# ECU_1v0.net
KiCad netlist of a schematic drawn in EAGLE
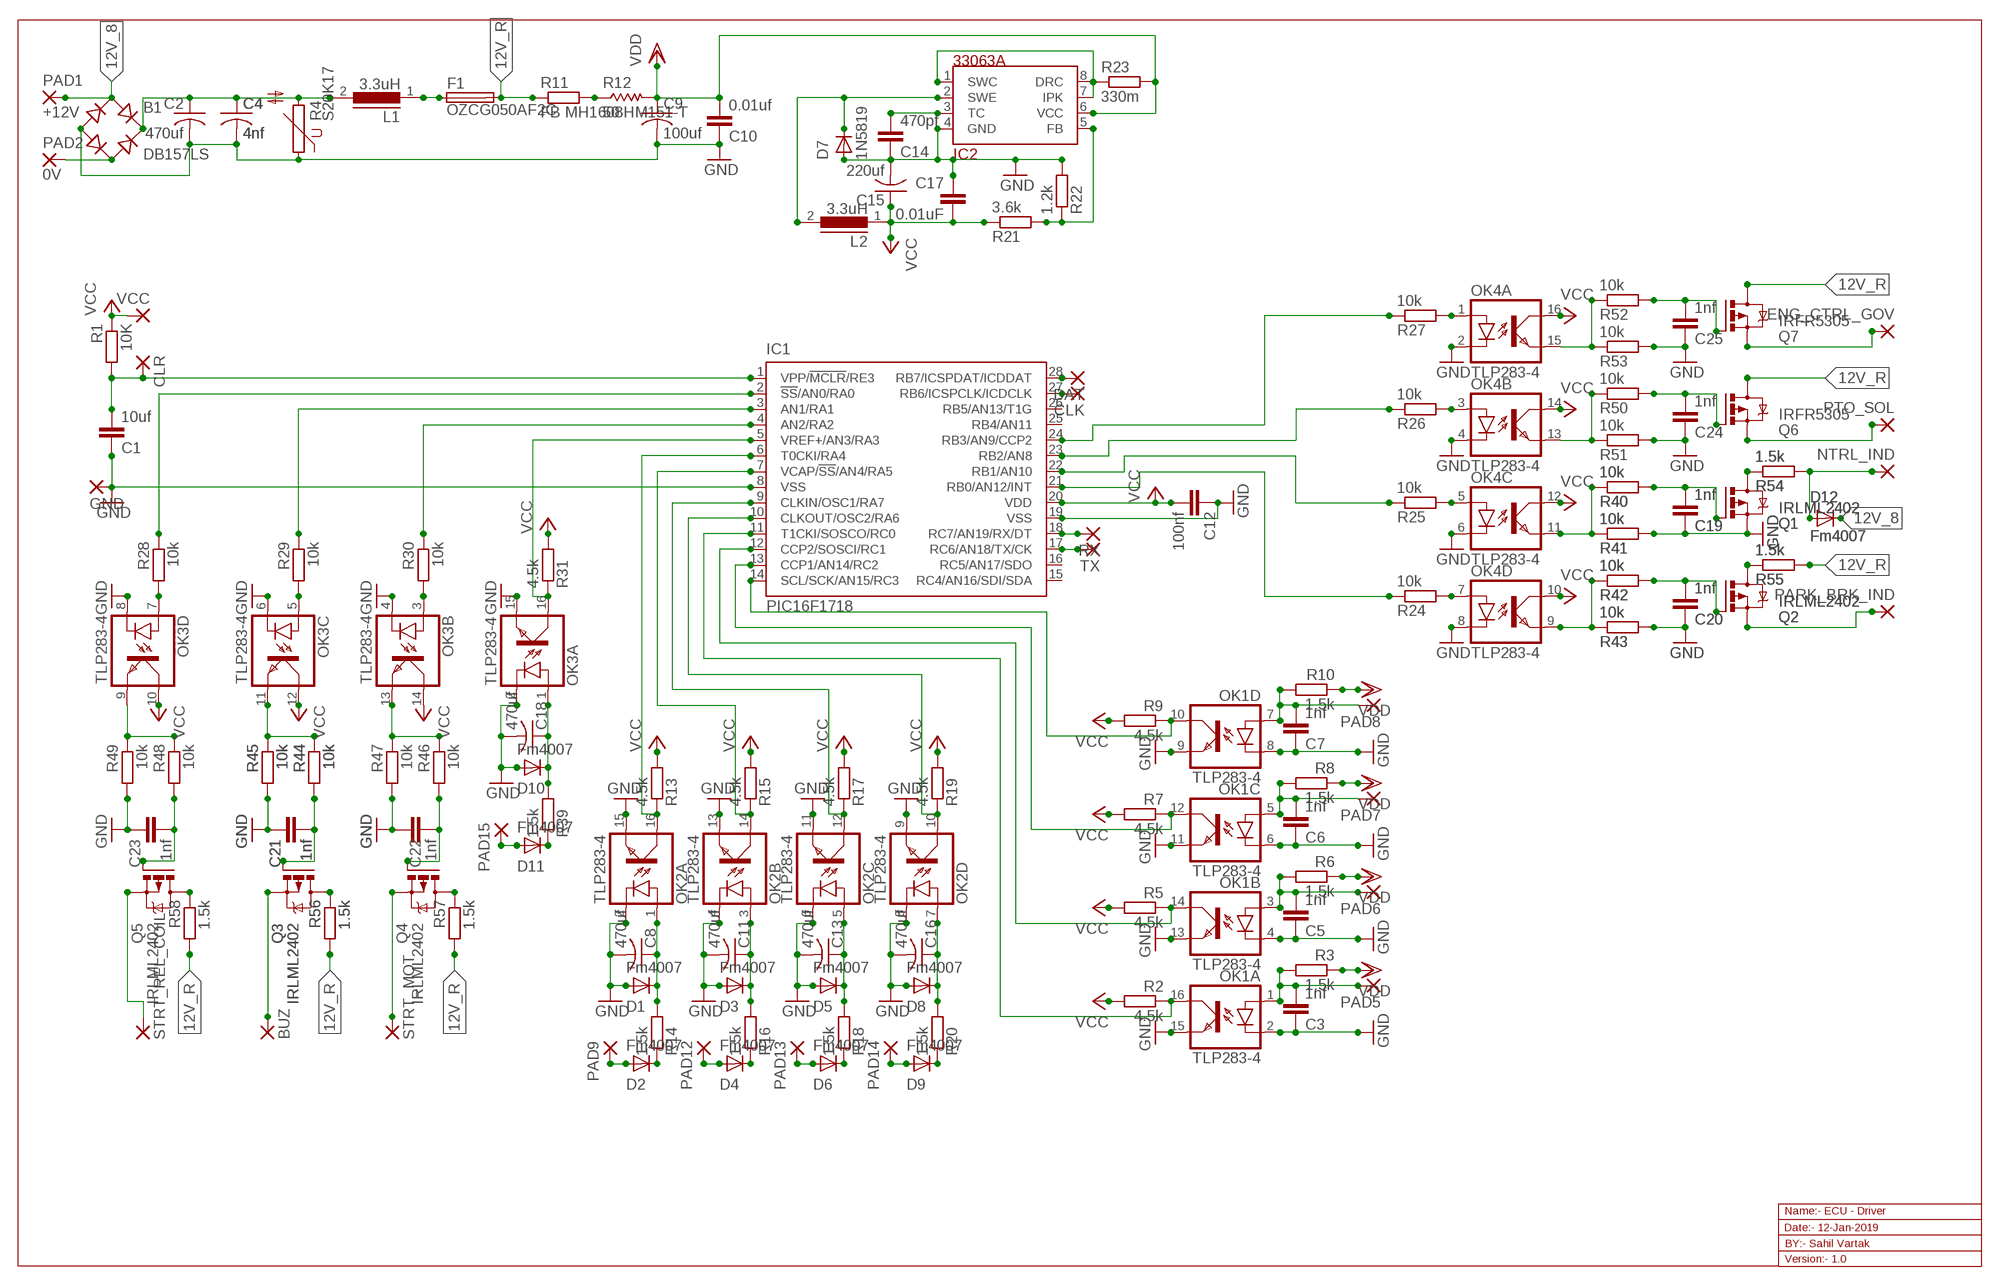
[diagram p0: schematic, sheet 1]

(export (version "E")
  (design (tool "Eeschema 10.0.6"))
  (components
    (comp (ref "B1")
      (value "DB157LS")
      (footprint "eagle-import:DBS")
      (libsource (lib "eagle-import") (part "DB?GS106"))
    )
    (comp (ref "BUZ")
      (value "2,54/1,1")
      (footprint "eagle-import:2,54_1,1")
      (libsource (lib "eagle-import") (part "2,54/1,1"))
    )
    (comp (ref "C1")
      (value "10uf")
      (footprint "eagle-import:C0603")
      (libsource (lib "eagle-import") (part "CC0603"))
    )
    (comp (ref "C2")
      (value "470uf")
      (footprint "eagle-import:C050-075X075")
      (libsource (lib "eagle-import") (part "resistor_C-US050-075X075"))
    )
    (comp (ref "C3")
      (value "1nf")
      (footprint "eagle-import:C0603")
      (libsource (lib "eagle-import") (part "CC0603"))
    )
    (comp (ref "C4")
      (value "4nf")
      (footprint "eagle-import:C050-045X075")
      (libsource (lib "eagle-import") (part "C-US050-045X075"))
    )
    (comp (ref "C5")
      (value "1nf")
      (footprint "eagle-import:C0603")
      (libsource (lib "eagle-import") (part "CC0603"))
    )
    (comp (ref "C6")
      (value "1nf")
      (footprint "eagle-import:C0603")
      (libsource (lib "eagle-import") (part "CC0603"))
    )
    (comp (ref "C7")
      (value "1nf")
      (footprint "eagle-import:C0603")
      (libsource (lib "eagle-import") (part "CC0603"))
    )
    (comp (ref "C8")
      (value "470uf")
      (footprint "eagle-import:C050-075X075")
      (libsource (lib "eagle-import") (part "resistor_C-US050-075X075"))
    )
    (comp (ref "C9")
      (value "100uf")
      (footprint "eagle-import:C025-025X050")
      (libsource (lib "eagle-import") (part "C-US025-025X050"))
    )
    (comp (ref "C10")
      (value "0.01uf")
      (footprint "eagle-import:C0603")
      (libsource (lib "eagle-import") (part "CC0603"))
    )
    (comp (ref "C11")
      (value "470uf")
      (footprint "eagle-import:C050-075X075")
      (libsource (lib "eagle-import") (part "resistor_C-US050-075X075"))
    )
    (comp (ref "C12")
      (value "100nf")
      (footprint "eagle-import:C0603")
      (libsource (lib "eagle-import") (part "CC0603"))
    )
    (comp (ref "C13")
      (value "470uf")
      (footprint "eagle-import:C050-075X075")
      (libsource (lib "eagle-import") (part "resistor_C-US050-075X075"))
    )
    (comp (ref "C14")
      (value "470pf")
      (footprint "eagle-import:C0603")
      (libsource (lib "eagle-import") (part "CC0603"))
    )
    (comp (ref "C15")
      (value "220uf")
      (footprint "eagle-import:C025-025X050")
      (libsource (lib "eagle-import") (part "C-US025-025X050"))
    )
    (comp (ref "C16")
      (value "470uf")
      (footprint "eagle-import:C050-075X075")
      (libsource (lib "eagle-import") (part "resistor_C-US050-075X075"))
    )
    (comp (ref "C17")
      (value "0.01uF")
      (footprint "eagle-import:C0603")
      (libsource (lib "eagle-import") (part "CC0603"))
    )
    (comp (ref "C18")
      (value "470uf")
      (footprint "eagle-import:C050-075X075")
      (libsource (lib "eagle-import") (part "resistor_C-US050-075X075"))
    )
    (comp (ref "C19")
      (value "1nf")
      (footprint "eagle-import:C0603")
      (libsource (lib "eagle-import") (part "CC0603"))
    )
    (comp (ref "C20")
      (value "1nf")
      (footprint "eagle-import:C0603")
      (libsource (lib "eagle-import") (part "CC0603"))
    )
    (comp (ref "C21")
      (value "1nf")
      (footprint "eagle-import:C0603")
      (libsource (lib "eagle-import") (part "CC0603"))
    )
    (comp (ref "C22")
      (value "1nf")
      (footprint "eagle-import:C0603")
      (libsource (lib "eagle-import") (part "CC0603"))
    )
    (comp (ref "C23")
      (value "1nf")
      (footprint "eagle-import:C0603")
      (libsource (lib "eagle-import") (part "CC0603"))
    )
    (comp (ref "C24")
      (value "1nf")
      (footprint "eagle-import:C0603")
      (libsource (lib "eagle-import") (part "CC0603"))
    )
    (comp (ref "C25")
      (value "1nf")
      (footprint "eagle-import:C0603")
      (libsource (lib "eagle-import") (part "CC0603"))
    )
    (comp (ref "CLK")
      (value "1,6/0,8")
      (footprint "eagle-import:1,6_0,8")
      (libsource (lib "eagle-import") (part "1,6/0,8"))
    )
    (comp (ref "CLR")
      (value "1,6/0,8")
      (footprint "eagle-import:1,6_0,8")
      (libsource (lib "eagle-import") (part "1,6/0,8"))
    )
    (comp (ref "D1")
      (value "Fm4007")
      (footprint "eagle-import:SMA-DO214AC")
      (libsource (lib "eagle-import") (part "GF1"))
    )
    (comp (ref "D2")
      (value "Fm4007")
      (footprint "eagle-import:SMA-DO214AC")
      (libsource (lib "eagle-import") (part "GF1"))
    )
    (comp (ref "D3")
      (value "Fm4007")
      (footprint "eagle-import:SMA-DO214AC")
      (libsource (lib "eagle-import") (part "GF1"))
    )
    (comp (ref "D4")
      (value "Fm4007")
      (footprint "eagle-import:SMA-DO214AC")
      (libsource (lib "eagle-import") (part "GF1"))
    )
    (comp (ref "D5")
      (value "Fm4007")
      (footprint "eagle-import:SMA-DO214AC")
      (libsource (lib "eagle-import") (part "GF1"))
    )
    (comp (ref "D6")
      (value "Fm4007")
      (footprint "eagle-import:SMA-DO214AC")
      (libsource (lib "eagle-import") (part "GF1"))
    )
    (comp (ref "D7")
      (value "1N5819")
      (footprint "eagle-import:SMA-DO214AC")
      (libsource (lib "eagle-import") (part "GF1"))
    )
    (comp (ref "D8")
      (value "Fm4007")
      (footprint "eagle-import:SMA-DO214AC")
      (libsource (lib "eagle-import") (part "GF1"))
    )
    (comp (ref "D9")
      (value "Fm4007")
      (footprint "eagle-import:SMA-DO214AC")
      (libsource (lib "eagle-import") (part "GF1"))
    )
    (comp (ref "D10")
      (value "Fm4007")
      (footprint "eagle-import:SMA-DO214AC")
      (libsource (lib "eagle-import") (part "GF1"))
    )
    (comp (ref "D11")
      (value "Fm4007")
      (footprint "eagle-import:SMA-DO214AC")
      (libsource (lib "eagle-import") (part "GF1"))
    )
    (comp (ref "D12")
      (value "Fm4007")
      (footprint "eagle-import:SMA-DO214AC")
      (libsource (lib "eagle-import") (part "GF1"))
    )
    (comp (ref "DAT")
      (value "1,6/0,8")
      (footprint "eagle-import:1,6_0,8")
      (libsource (lib "eagle-import") (part "1,6/0,8"))
    )
    (comp (ref "ENG_CTRL_GOV")
      (value "2,54/1,1")
      (footprint "eagle-import:2,54_1,1")
      (libsource (lib "eagle-import") (part "2,54/1,1"))
    )
    (comp (ref "F1")
      (value "OZCG050AF2C")
      (footprint "eagle-import:RES_FUSE")
      (libsource (lib "eagle-import") (part "RES_FUSE"))
    )
    (comp (ref "GND")
      (value "1,6/0,8")
      (footprint "eagle-import:1,6_0,8")
      (libsource (lib "eagle-import") (part "1,6/0,8"))
    )
    (comp (ref "IC1")
      (value "PIC16F1718")
      (footprint "eagle-import:SO28W")
      (libsource (lib "eagle-import") (part "PIC16F1516/18SO"))
    )
    (comp (ref "IC2")
      (value "33063A")
      (footprint "eagle-import:D_R-PDSO-G8")
      (libsource (lib "eagle-import") (part "33063A"))
    )
    (comp (ref "L1")
      (value "3.3uH")
      (footprint "eagle-import:82114R")
      (libsource (lib "eagle-import") (part "82114R"))
    )
    (comp (ref "L2")
      (value "3.3uH")
      (footprint "eagle-import:82114R")
      (libsource (lib "eagle-import") (part "82114R"))
    )
    (comp (ref "NTRL_IND")
      (value "2,54/1,1")
      (footprint "eagle-import:2,54_1,1")
      (libsource (lib "eagle-import") (part "2,54/1,1"))
    )
    (comp (ref "OK1")
      (value "TLP283-4")
      (footprint "eagle-import:MINI-FLAT-16")
      (libsource (lib "eagle-import") (part "TLP283-4"))
    )
    (comp (ref "OK2")
      (value "TLP283-4")
      (footprint "eagle-import:MINI-FLAT-16")
      (libsource (lib "eagle-import") (part "TLP283-4"))
    )
    (comp (ref "OK3")
      (value "TLP283-4")
      (footprint "eagle-import:MINI-FLAT-16")
      (libsource (lib "eagle-import") (part "TLP283-4"))
    )
    (comp (ref "OK4")
      (value "TLP283-4")
      (footprint "eagle-import:MINI-FLAT-16")
      (libsource (lib "eagle-import") (part "TLP283-4"))
    )
    (comp (ref "PAD1")
      (value "+12V")
      (footprint "eagle-import:2,54_1,1")
      (libsource (lib "eagle-import") (part "2,54/1,1"))
    )
    (comp (ref "PAD2")
      (value "0V")
      (footprint "eagle-import:2,54_1,1")
      (libsource (lib "eagle-import") (part "2,54/1,1"))
    )
    (comp (ref "PAD5")
      (value "2,54/1,1")
      (footprint "eagle-import:2,54_1,1")
      (libsource (lib "eagle-import") (part "2,54/1,1"))
    )
    (comp (ref "PAD6")
      (value "2,54/1,1")
      (footprint "eagle-import:2,54_1,1")
      (libsource (lib "eagle-import") (part "2,54/1,1"))
    )
    (comp (ref "PAD7")
      (value "2,54/1,1")
      (footprint "eagle-import:2,54_1,1")
      (libsource (lib "eagle-import") (part "2,54/1,1"))
    )
    (comp (ref "PAD8")
      (value "2,54/1,1")
      (footprint "eagle-import:2,54_1,1")
      (libsource (lib "eagle-import") (part "2,54/1,1"))
    )
    (comp (ref "PAD9")
      (value "2,54/1,1")
      (footprint "eagle-import:2,54_1,1")
      (libsource (lib "eagle-import") (part "2,54/1,1"))
    )
    (comp (ref "PAD12")
      (value "2,54/1,1")
      (footprint "eagle-import:2,54_1,1")
      (libsource (lib "eagle-import") (part "2,54/1,1"))
    )
    (comp (ref "PAD13")
      (value "2,54/1,1")
      (footprint "eagle-import:2,54_1,1")
      (libsource (lib "eagle-import") (part "2,54/1,1"))
    )
    (comp (ref "PAD14")
      (value "2,54/1,1")
      (footprint "eagle-import:2,54_1,1")
      (libsource (lib "eagle-import") (part "2,54/1,1"))
    )
    (comp (ref "PAD15")
      (value "2,54/1,1")
      (footprint "eagle-import:2,54_1,1")
      (libsource (lib "eagle-import") (part "2,54/1,1"))
    )
    (comp (ref "PARK_BRK_IND")
      (value "2,54/1,1")
      (footprint "eagle-import:2,54_1,1")
      (libsource (lib "eagle-import") (part "2,54/1,1"))
    )
    (comp (ref "PTO_SOL")
      (value "2,54/1,1")
      (footprint "eagle-import:2,54_1,1")
      (libsource (lib "eagle-import") (part "2,54/1,1"))
    )
    (comp (ref "Q1")
      (value "IRLML2402")
      (footprint "eagle-import:MICRO3")
      (libsource (lib "eagle-import") (part "IRLML5203"))
    )
    (comp (ref "Q2")
      (value "IRLML2402")
      (footprint "eagle-import:MICRO3")
      (libsource (lib "eagle-import") (part "IRLML5203"))
    )
    (comp (ref "Q3")
      (value "IRLML2402")
      (footprint "eagle-import:MICRO3")
      (libsource (lib "eagle-import") (part "IRLML5203"))
    )
    (comp (ref "Q4")
      (value "IRLML2402")
      (footprint "eagle-import:MICRO3")
      (libsource (lib "eagle-import") (part "IRLML5203"))
    )
    (comp (ref "Q5")
      (value "IRLML2402")
      (footprint "eagle-import:MICRO3")
      (libsource (lib "eagle-import") (part "IRLML5203"))
    )
    (comp (ref "Q6")
      (value "IRFR5305")
      (footprint "eagle-import:D-PAK_TO252AA")
      (libsource (lib "eagle-import") (part "IRF?5305R"))
    )
    (comp (ref "Q7")
      (value "IRFR5305")
      (footprint "eagle-import:D-PAK_TO252AA")
      (libsource (lib "eagle-import") (part "IRF?5305R"))
    )
    (comp (ref "R1")
      (value "10K")
      (footprint "eagle-import:R0603")
      (libsource (lib "eagle-import") (part "RR0603"))
    )
    (comp (ref "R2")
      (value "4.5k")
      (footprint "eagle-import:R0603")
      (libsource (lib "eagle-import") (part "RR0603"))
    )
    (comp (ref "R3")
      (value "1.5k")
      (footprint "eagle-import:R0603")
      (libsource (lib "eagle-import") (part "RR0603"))
    )
    (comp (ref "R4")
      (value "S20K17")
      (footprint "eagle-import:S14K17")
      (libsource (lib "eagle-import") (part "S14K17"))
    )
    (comp (ref "R5")
      (value "4.5k")
      (footprint "eagle-import:R0603")
      (libsource (lib "eagle-import") (part "RR0603"))
    )
    (comp (ref "R6")
      (value "1.5k")
      (footprint "eagle-import:R0603")
      (libsource (lib "eagle-import") (part "RR0603"))
    )
    (comp (ref "R7")
      (value "4.5k")
      (footprint "eagle-import:R0603")
      (libsource (lib "eagle-import") (part "RR0603"))
    )
    (comp (ref "R8")
      (value "1.5k")
      (footprint "eagle-import:R0603")
      (libsource (lib "eagle-import") (part "RR0603"))
    )
    (comp (ref "R9")
      (value "4.5k")
      (footprint "eagle-import:R0603")
      (libsource (lib "eagle-import") (part "RR0603"))
    )
    (comp (ref "R10")
      (value "1.5k")
      (footprint "eagle-import:R0603")
      (libsource (lib "eagle-import") (part "RR0603"))
    )
    (comp (ref "R11")
      (value "FB MH1608HM151-T")
      (footprint "eagle-import:R0603")
      (libsource (lib "eagle-import") (part "R-EU_R0603"))
    )
    (comp (ref "R12")
      (value "50")
      (footprint "eagle-import:WSC2515")
      (libsource (lib "eagle-import") (part "R-US_WSC2515"))
    )
    (comp (ref "R13")
      (value "4.5k")
      (footprint "eagle-import:R0603")
      (libsource (lib "eagle-import") (part "RR0603"))
    )
    (comp (ref "R14")
      (value "1.5k")
      (footprint "eagle-import:R0603")
      (libsource (lib "eagle-import") (part "RR0603"))
    )
    (comp (ref "R15")
      (value "4.5k")
      (footprint "eagle-import:R0603")
      (libsource (lib "eagle-import") (part "RR0603"))
    )
    (comp (ref "R16")
      (value "1.5k")
      (footprint "eagle-import:R0603")
      (libsource (lib "eagle-import") (part "RR0603"))
    )
    (comp (ref "R17")
      (value "4.5k")
      (footprint "eagle-import:R0603")
      (libsource (lib "eagle-import") (part "RR0603"))
    )
    (comp (ref "R18")
      (value "1.5k")
      (footprint "eagle-import:R0603")
      (libsource (lib "eagle-import") (part "RR0603"))
    )
    (comp (ref "R19")
      (value "4.5k")
      (footprint "eagle-import:R0603")
      (libsource (lib "eagle-import") (part "RR0603"))
    )
    (comp (ref "R20")
      (value "1.5k")
      (footprint "eagle-import:R0603")
      (libsource (lib "eagle-import") (part "RR0603"))
    )
    (comp (ref "R21")
      (value "3.6k")
      (footprint "eagle-import:R0603")
      (libsource (lib "eagle-import") (part "RR0603"))
    )
    (comp (ref "R22")
      (value "1.2k")
      (footprint "eagle-import:R0603")
      (libsource (lib "eagle-import") (part "RR0603"))
    )
    (comp (ref "R23")
      (value "330m")
      (footprint "eagle-import:R2010")
      (libsource (lib "eagle-import") (part "RR2010"))
    )
    (comp (ref "R24")
      (value "10k")
      (footprint "eagle-import:R0603")
      (libsource (lib "eagle-import") (part "RR0603"))
    )
    (comp (ref "R25")
      (value "10k")
      (footprint "eagle-import:R0603")
      (libsource (lib "eagle-import") (part "RR0603"))
    )
    (comp (ref "R26")
      (value "10k")
      (footprint "eagle-import:R0603")
      (libsource (lib "eagle-import") (part "RR0603"))
    )
    (comp (ref "R27")
      (value "10k")
      (footprint "eagle-import:R0603")
      (libsource (lib "eagle-import") (part "RR0603"))
    )
    (comp (ref "R28")
      (value "10k")
      (footprint "eagle-import:R0603")
      (libsource (lib "eagle-import") (part "RR0603"))
    )
    (comp (ref "R29")
      (value "10k")
      (footprint "eagle-import:R0603")
      (libsource (lib "eagle-import") (part "RR0603"))
    )
    (comp (ref "R30")
      (value "10k")
      (footprint "eagle-import:R0603")
      (libsource (lib "eagle-import") (part "RR0603"))
    )
    (comp (ref "R31")
      (value "4.5k")
      (footprint "eagle-import:R0603")
      (libsource (lib "eagle-import") (part "RR0603"))
    )
    (comp (ref "R39")
      (value "1.5k")
      (footprint "eagle-import:R0603")
      (libsource (lib "eagle-import") (part "RR0603"))
    )
    (comp (ref "R40")
      (value "10k")
      (footprint "eagle-import:R0603")
      (libsource (lib "eagle-import") (part "RR0603"))
    )
    (comp (ref "R41")
      (value "10k")
      (footprint "eagle-import:R0603")
      (libsource (lib "eagle-import") (part "RR0603"))
    )
    (comp (ref "R42")
      (value "10k")
      (footprint "eagle-import:R0603")
      (libsource (lib "eagle-import") (part "RR0603"))
    )
    (comp (ref "R43")
      (value "10k")
      (footprint "eagle-import:R0603")
      (libsource (lib "eagle-import") (part "RR0603"))
    )
    (comp (ref "R44")
      (value "10k")
      (footprint "eagle-import:R0603")
      (libsource (lib "eagle-import") (part "RR0603"))
    )
    (comp (ref "R45")
      (value "10k")
      (footprint "eagle-import:R0603")
      (libsource (lib "eagle-import") (part "RR0603"))
    )
    (comp (ref "R46")
      (value "10k")
      (footprint "eagle-import:R0603")
      (libsource (lib "eagle-import") (part "RR0603"))
    )
    (comp (ref "R47")
      (value "10k")
      (footprint "eagle-import:R0603")
      (libsource (lib "eagle-import") (part "RR0603"))
    )
    (comp (ref "R48")
      (value "10k")
      (footprint "eagle-import:R0603")
      (libsource (lib "eagle-import") (part "RR0603"))
    )
    (comp (ref "R49")
      (value "10k")
      (footprint "eagle-import:R0603")
      (libsource (lib "eagle-import") (part "RR0603"))
    )
    (comp (ref "R50")
      (value "10k")
      (footprint "eagle-import:R0603")
      (libsource (lib "eagle-import") (part "RR0603"))
    )
    (comp (ref "R51")
      (value "10k")
      (footprint "eagle-import:R0603")
      (libsource (lib "eagle-import") (part "RR0603"))
    )
    (comp (ref "R52")
      (value "10k")
      (footprint "eagle-import:R0603")
      (libsource (lib "eagle-import") (part "RR0603"))
    )
    (comp (ref "R53")
      (value "10k")
      (footprint "eagle-import:R0603")
      (libsource (lib "eagle-import") (part "RR0603"))
    )
    (comp (ref "R54")
      (value "1.5k")
      (footprint "eagle-import:R0603")
      (libsource (lib "eagle-import") (part "RR0603"))
    )
    (comp (ref "R55")
      (value "1.5k")
      (footprint "eagle-import:R0603")
      (libsource (lib "eagle-import") (part "RR0603"))
    )
    (comp (ref "R56")
      (value "1.5k")
      (footprint "eagle-import:R0603")
      (libsource (lib "eagle-import") (part "RR0603"))
    )
    (comp (ref "R57")
      (value "1.5k")
      (footprint "eagle-import:R0603")
      (libsource (lib "eagle-import") (part "RR0603"))
    )
    (comp (ref "R58")
      (value "1.5k")
      (footprint "eagle-import:R0603")
      (libsource (lib "eagle-import") (part "RR0603"))
    )
    (comp (ref "RX")
      (value "1,6/0,8")
      (footprint "eagle-import:1,6_0,8")
      (libsource (lib "eagle-import") (part "1,6/0,8"))
    )
    (comp (ref "STRT_MOT")
      (value "2,54/1,1")
      (footprint "eagle-import:2,54_1,1")
      (libsource (lib "eagle-import") (part "2,54/1,1"))
    )
    (comp (ref "STRT_REL_COIL")
      (value "2,54/1,1")
      (footprint "eagle-import:2,54_1,1")
      (libsource (lib "eagle-import") (part "2,54/1,1"))
    )
    (comp (ref "TX")
      (value "1,6/0,8")
      (footprint "eagle-import:1,6_0,8")
      (libsource (lib "eagle-import") (part "1,6/0,8"))
    )
    (comp (ref "VCC")
      (value "1,6/0,8")
      (footprint "eagle-import:1,6_0,8")
      (libsource (lib "eagle-import") (part "1,6/0,8"))
    )
  )
  (nets
    (net (code "1") (name "12V_8") (class "Default")
      (node (ref "B1") (pin "AC1") (pinfunction "AC1_AC1") (pintype "passive"))
      (node (ref "D12") (pin "K") (pinfunction "C_K") (pintype "passive"))
      (node (ref "PAD1") (pin "1") (pinfunction "P_1") (pintype "passive"))
    )
    (net (code "2") (name "12V_R") (class "Default")
      (node (ref "F1") (pin "2") (pinfunction "4_2") (pintype "passive"))
      (node (ref "Q6") (pin "4") (pinfunction "D_4") (pintype "passive"))
      (node (ref "Q7") (pin "4") (pinfunction "D_4") (pintype "passive"))
      (node (ref "R11") (pin "1") (pinfunction "1_1") (pintype "passive"))
      (node (ref "R55") (pin "2") (pinfunction "2_2") (pintype "passive"))
      (node (ref "R56") (pin "2") (pinfunction "2_2") (pintype "passive"))
      (node (ref "R57") (pin "2") (pinfunction "2_2") (pintype "passive"))
      (node (ref "R58") (pin "2") (pinfunction "2_2") (pintype "passive"))
    )
    (net (code "3") (name "GND") (class "Default")
      (node (ref "B1") (pin "-") (pinfunction "-_-") (pintype "passive"))
      (node (ref "C1") (pin "1") (pinfunction "1_1") (pintype "passive"))
      (node (ref "C10") (pin "1") (pinfunction "1_1") (pintype "passive"))
      (node (ref "C11") (pin "2") (pinfunction "2_2") (pintype "passive"))
      (node (ref "C12") (pin "1") (pinfunction "1_1") (pintype "passive"))
      (node (ref "C13") (pin "2") (pinfunction "2_2") (pintype "passive"))
      (node (ref "C14") (pin "1") (pinfunction "1_1") (pintype "passive"))
      (node (ref "C15") (pin "2") (pinfunction "2_2") (pintype "passive"))
      (node (ref "C16") (pin "2") (pinfunction "2_2") (pintype "passive"))
      (node (ref "C17") (pin "1") (pinfunction "1_1") (pintype "passive"))
      (node (ref "C18") (pin "2") (pinfunction "2_2") (pintype "passive"))
      (node (ref "C19") (pin "1") (pinfunction "1_1") (pintype "passive"))
      (node (ref "C2") (pin "2") (pinfunction "2_2") (pintype "passive"))
      (node (ref "C20") (pin "1") (pinfunction "1_1") (pintype "passive"))
      (node (ref "C21") (pin "1") (pinfunction "1_1") (pintype "passive"))
      (node (ref "C22") (pin "1") (pinfunction "1_1") (pintype "passive"))
      (node (ref "C23") (pin "1") (pinfunction "1_1") (pintype "passive"))
      (node (ref "C24") (pin "1") (pinfunction "1_1") (pintype "passive"))
      (node (ref "C25") (pin "1") (pinfunction "1_1") (pintype "passive"))
      (node (ref "C3") (pin "1") (pinfunction "1_1") (pintype "passive"))
      (node (ref "C4") (pin "2") (pinfunction "2_2") (pintype "passive"))
      (node (ref "C5") (pin "1") (pinfunction "1_1") (pintype "passive"))
      (node (ref "C6") (pin "1") (pinfunction "1_1") (pintype "passive"))
      (node (ref "C7") (pin "1") (pinfunction "1_1") (pintype "passive"))
      (node (ref "C8") (pin "2") (pinfunction "2_2") (pintype "passive"))
      (node (ref "C9") (pin "2") (pinfunction "2_2") (pintype "passive"))
      (node (ref "D1") (pin "A") (pinfunction "A_A") (pintype "passive"))
      (node (ref "D10") (pin "A") (pinfunction "A_A") (pintype "passive"))
      (node (ref "D3") (pin "A") (pinfunction "A_A") (pintype "passive"))
      (node (ref "D5") (pin "A") (pinfunction "A_A") (pintype "passive"))
      (node (ref "D7") (pin "A") (pinfunction "A_A") (pintype "passive"))
      (node (ref "D8") (pin "A") (pinfunction "A_A") (pintype "passive"))
      (node (ref "GND") (pin "1") (pinfunction "P_1") (pintype "passive"))
      (node (ref "IC1") (pin "19") (pinfunction "VSS_19") (pintype "power_in"))
      (node (ref "IC1") (pin "8") (pinfunction "VSS_8") (pintype "power_in"))
      (node (ref "IC2") (pin "4") (pinfunction "GND_4") (pintype "bidirectional"))
      (node (ref "OK1") (pin "11") (pinfunction "EMIT_11") (pintype "passive"))
      (node (ref "OK1") (pin "13") (pinfunction "EMIT_13") (pintype "passive"))
      (node (ref "OK1") (pin "15") (pinfunction "EMIT_15") (pintype "passive"))
      (node (ref "OK1") (pin "2") (pinfunction "C_2") (pintype "passive"))
      (node (ref "OK1") (pin "4") (pinfunction "C_4") (pintype "passive"))
      (node (ref "OK1") (pin "6") (pinfunction "C_6") (pintype "passive"))
      (node (ref "OK1") (pin "8") (pinfunction "C_8") (pintype "passive"))
      (node (ref "OK1") (pin "9") (pinfunction "EMIT_9") (pintype "passive"))
      (node (ref "OK2") (pin "11") (pinfunction "EMIT_11") (pintype "passive"))
      (node (ref "OK2") (pin "13") (pinfunction "EMIT_13") (pintype "passive"))
      (node (ref "OK2") (pin "15") (pinfunction "EMIT_15") (pintype "passive"))
      (node (ref "OK2") (pin "2") (pinfunction "C_2") (pintype "passive"))
      (node (ref "OK2") (pin "4") (pinfunction "C_4") (pintype "passive"))
      (node (ref "OK2") (pin "6") (pinfunction "C_6") (pintype "passive"))
      (node (ref "OK2") (pin "8") (pinfunction "C_8") (pintype "passive"))
      (node (ref "OK2") (pin "9") (pinfunction "EMIT_9") (pintype "passive"))
      (node (ref "OK3") (pin "15") (pinfunction "EMIT_15") (pintype "passive"))
      (node (ref "OK3") (pin "2") (pinfunction "C_2") (pintype "passive"))
      (node (ref "OK3") (pin "4") (pinfunction "C_4") (pintype "passive"))
      (node (ref "OK3") (pin "6") (pinfunction "C_6") (pintype "passive"))
      (node (ref "OK3") (pin "8") (pinfunction "C_8") (pintype "passive"))
      (node (ref "OK4") (pin "2") (pinfunction "C_2") (pintype "passive"))
      (node (ref "OK4") (pin "4") (pinfunction "C_4") (pintype "passive"))
      (node (ref "OK4") (pin "6") (pinfunction "C_6") (pintype "passive"))
      (node (ref "OK4") (pin "8") (pinfunction "C_8") (pintype "passive"))
      (node (ref "Q1") (pin "2") (pinfunction "S_2") (pintype "passive"))
      (node (ref "R22") (pin "2") (pinfunction "2_2") (pintype "passive"))
      (node (ref "R4") (pin "1") (pinfunction "1_1") (pintype "passive"))
      (node (ref "R41") (pin "2") (pinfunction "2_2") (pintype "passive"))
      (node (ref "R43") (pin "2") (pinfunction "2_2") (pintype "passive"))
      (node (ref "R45") (pin "2") (pinfunction "2_2") (pintype "passive"))
      (node (ref "R47") (pin "2") (pinfunction "2_2") (pintype "passive"))
      (node (ref "R49") (pin "2") (pinfunction "2_2") (pintype "passive"))
      (node (ref "R51") (pin "2") (pinfunction "2_2") (pintype "passive"))
      (node (ref "R53") (pin "2") (pinfunction "2_2") (pintype "passive"))
    )
    (net (code "4") (name "Net-(B1-Pad+)") (class "Default")
      (node (ref "B1") (pin "+") (pinfunction "+_+") (pintype "passive"))
      (node (ref "C2") (pin "1") (pinfunction "1_1") (pintype "passive"))
      (node (ref "C4") (pin "1") (pinfunction "1_1") (pintype "passive"))
      (node (ref "L1") (pin "2") (pinfunction "2_2") (pintype "passive"))
      (node (ref "R4") (pin "2") (pinfunction "2_2") (pintype "passive"))
    )
    (net (code "5") (name "Net-(BUZ-P)") (class "Default")
      (node (ref "BUZ") (pin "1") (pinfunction "P_1") (pintype "passive"))
      (node (ref "Q3") (pin "2") (pinfunction "S_2") (pintype "passive"))
    )
    (net (code "6") (name "Net-(CLK-P)") (class "Default")
      (node (ref "CLK") (pin "1") (pinfunction "P_1") (pintype "passive"))
      (node (ref "IC1") (pin "27") (pinfunction "RB6/ICSPCLK/ICDCLK_27") (pintype "bidirectional"))
    )
    (net (code "7") (name "Net-(CLR-P)") (class "Default")
      (node (ref "C1") (pin "2") (pinfunction "2_2") (pintype "passive"))
      (node (ref "CLR") (pin "1") (pinfunction "P_1") (pintype "passive"))
      (node (ref "IC1") (pin "1") (pinfunction "VPP/~{MCLR}/RE3_1") (pintype "bidirectional"))
      (node (ref "R1") (pin "2") (pinfunction "2_2") (pintype "passive"))
    )
    (net (code "8") (name "Net-(D1-C)") (class "Default")
      (node (ref "C8") (pin "1") (pinfunction "1_1") (pintype "passive"))
      (node (ref "D1") (pin "K") (pinfunction "C_K") (pintype "passive"))
      (node (ref "OK2") (pin "1") (pinfunction "A_1") (pintype "passive"))
      (node (ref "R14") (pin "2") (pinfunction "2_2") (pintype "passive"))
    )
    (net (code "9") (name "Net-(D2-C)") (class "Default")
      (node (ref "D2") (pin "K") (pinfunction "C_K") (pintype "passive"))
      (node (ref "R14") (pin "1") (pinfunction "1_1") (pintype "passive"))
    )
    (net (code "10") (name "Net-(D3-C)") (class "Default")
      (node (ref "C11") (pin "1") (pinfunction "1_1") (pintype "passive"))
      (node (ref "D3") (pin "K") (pinfunction "C_K") (pintype "passive"))
      (node (ref "OK2") (pin "3") (pinfunction "A_3") (pintype "passive"))
      (node (ref "R16") (pin "2") (pinfunction "2_2") (pintype "passive"))
    )
    (net (code "11") (name "Net-(D4-C)") (class "Default")
      (node (ref "D4") (pin "K") (pinfunction "C_K") (pintype "passive"))
      (node (ref "R16") (pin "1") (pinfunction "1_1") (pintype "passive"))
    )
    (net (code "12") (name "Net-(D5-C)") (class "Default")
      (node (ref "C13") (pin "1") (pinfunction "1_1") (pintype "passive"))
      (node (ref "D5") (pin "K") (pinfunction "C_K") (pintype "passive"))
      (node (ref "OK2") (pin "5") (pinfunction "A_5") (pintype "passive"))
      (node (ref "R18") (pin "2") (pinfunction "2_2") (pintype "passive"))
    )
    (net (code "13") (name "Net-(D6-C)") (class "Default")
      (node (ref "D6") (pin "K") (pinfunction "C_K") (pintype "passive"))
      (node (ref "R18") (pin "1") (pinfunction "1_1") (pintype "passive"))
    )
    (net (code "14") (name "Net-(D7-C)") (class "Default")
      (node (ref "D7") (pin "K") (pinfunction "C_K") (pintype "passive"))
      (node (ref "IC2") (pin "2") (pinfunction "SWE_2") (pintype "bidirectional"))
      (node (ref "L2") (pin "2") (pinfunction "2_2") (pintype "passive"))
    )
    (net (code "15") (name "Net-(D8-C)") (class "Default")
      (node (ref "C16") (pin "1") (pinfunction "1_1") (pintype "passive"))
      (node (ref "D8") (pin "K") (pinfunction "C_K") (pintype "passive"))
      (node (ref "OK2") (pin "7") (pinfunction "A_7") (pintype "passive"))
      (node (ref "R20") (pin "2") (pinfunction "2_2") (pintype "passive"))
    )
    (net (code "16") (name "Net-(D9-C)") (class "Default")
      (node (ref "D9") (pin "K") (pinfunction "C_K") (pintype "passive"))
      (node (ref "R20") (pin "1") (pinfunction "1_1") (pintype "passive"))
    )
    (net (code "17") (name "Net-(D10-C)") (class "Default")
      (node (ref "C18") (pin "1") (pinfunction "1_1") (pintype "passive"))
      (node (ref "D10") (pin "K") (pinfunction "C_K") (pintype "passive"))
      (node (ref "OK3") (pin "1") (pinfunction "A_1") (pintype "passive"))
      (node (ref "R39") (pin "2") (pinfunction "2_2") (pintype "passive"))
    )
    (net (code "18") (name "Net-(D11-C)") (class "Default")
      (node (ref "D11") (pin "K") (pinfunction "C_K") (pintype "passive"))
      (node (ref "R39") (pin "1") (pinfunction "1_1") (pintype "passive"))
    )
    (net (code "19") (name "Net-(DAT-P)") (class "Default")
      (node (ref "DAT") (pin "1") (pinfunction "P_1") (pintype "passive"))
      (node (ref "IC1") (pin "28") (pinfunction "RB7/ICSPDAT/ICDDAT_28") (pintype "bidirectional"))
    )
    (net (code "20") (name "Net-(ENG_CTRL_GOV-P)") (class "Default")
      (node (ref "ENG_CTRL_GOV") (pin "1") (pinfunction "P_1") (pintype "passive"))
      (node (ref "Q7") (pin "3") (pinfunction "S_3") (pintype "passive"))
    )
    (net (code "21") (name "Net-(F1-3)") (class "Default")
      (node (ref "F1") (pin "1") (pinfunction "3_1") (pintype "passive"))
      (node (ref "L1") (pin "1") (pinfunction "1_1") (pintype "passive"))
    )
    (net (code "22") (name "Net-(IC1-AN1{slash}RA1)") (class "Default")
      (node (ref "IC1") (pin "3") (pinfunction "AN1/RA1_3") (pintype "bidirectional"))
      (node (ref "R29") (pin "1") (pinfunction "1_1") (pintype "passive"))
    )
    (net (code "23") (name "Net-(IC1-AN2{slash}RA2)") (class "Default")
      (node (ref "IC1") (pin "4") (pinfunction "AN2/RA2_4") (pintype "bidirectional"))
      (node (ref "R30") (pin "1") (pinfunction "1_1") (pintype "passive"))
    )
    (net (code "24") (name "Net-(IC1-CCP1{slash}AN14{slash}RC2)") (class "Default")
      (node (ref "IC1") (pin "13") (pinfunction "CCP1/AN14/RC2_13") (pintype "bidirectional"))
      (node (ref "OK1") (pin "12") (pinfunction "COL_12") (pintype "passive"))
      (node (ref "R7") (pin "1") (pinfunction "1_1") (pintype "passive"))
    )
    (net (code "25") (name "Net-(IC1-CCP2{slash}SOSCI{slash}RC1)") (class "Default")
      (node (ref "IC1") (pin "12") (pinfunction "CCP2/SOSCI/RC1_12") (pintype "bidirectional"))
      (node (ref "OK1") (pin "14") (pinfunction "COL_14") (pintype "passive"))
      (node (ref "R5") (pin "1") (pinfunction "1_1") (pintype "passive"))
    )
    (net (code "26") (name "Net-(IC1-CLKIN{slash}OSC1{slash}RA7)") (class "Default")
      (node (ref "IC1") (pin "9") (pinfunction "CLKIN/OSC1/RA7_9") (pintype "bidirectional"))
      (node (ref "OK2") (pin "12") (pinfunction "COL_12") (pintype "passive"))
      (node (ref "R17") (pin "1") (pinfunction "1_1") (pintype "passive"))
    )
    (net (code "27") (name "Net-(IC1-CLKOUT{slash}OSC2{slash}RA6)") (class "Default")
      (node (ref "IC1") (pin "10") (pinfunction "CLKOUT/OSC2/RA6_10") (pintype "bidirectional"))
      (node (ref "OK2") (pin "10") (pinfunction "COL_10") (pintype "passive"))
      (node (ref "R19") (pin "1") (pinfunction "1_1") (pintype "passive"))
    )
    (net (code "28") (name "Net-(IC1-RB0{slash}AN12{slash}INT)") (class "Default")
      (node (ref "IC1") (pin "21") (pinfunction "RB0/AN12/INT_21") (pintype "bidirectional"))
      (node (ref "R24") (pin "1") (pinfunction "1_1") (pintype "passive"))
    )
    (net (code "29") (name "Net-(IC1-RB1{slash}AN10)") (class "Default")
      (node (ref "IC1") (pin "22") (pinfunction "RB1/AN10_22") (pintype "bidirectional"))
      (node (ref "R25") (pin "1") (pinfunction "1_1") (pintype "passive"))
    )
    (net (code "30") (name "Net-(IC1-RB2{slash}AN8)") (class "Default")
      (node (ref "IC1") (pin "23") (pinfunction "RB2/AN8_23") (pintype "bidirectional"))
      (node (ref "R26") (pin "1") (pinfunction "1_1") (pintype "passive"))
    )
    (net (code "31") (name "Net-(IC1-RB3{slash}AN9{slash}CCP2)") (class "Default")
      (node (ref "IC1") (pin "24") (pinfunction "RB3/AN9/CCP2_24") (pintype "bidirectional"))
      (node (ref "R27") (pin "1") (pinfunction "1_1") (pintype "passive"))
    )
    (net (code "32") (name "Net-(IC1-RC6{slash}AN18{slash}TX{slash}CK)") (class "Default")
      (node (ref "IC1") (pin "17") (pinfunction "RC6/AN18/TX/CK_17") (pintype "bidirectional"))
      (node (ref "TX") (pin "1") (pinfunction "P_1") (pintype "passive"))
    )
    (net (code "33") (name "Net-(IC1-RC7{slash}AN19{slash}RX{slash}DT)") (class "Default")
      (node (ref "IC1") (pin "18") (pinfunction "RC7/AN19/RX/DT_18") (pintype "bidirectional"))
      (node (ref "RX") (pin "1") (pinfunction "P_1") (pintype "passive"))
    )
    (net (code "34") (name "Net-(IC1-SCL{slash}SCK{slash}AN15{slash}RC3)") (class "Default")
      (node (ref "IC1") (pin "14") (pinfunction "SCL/SCK/AN15/RC3_14") (pintype "bidirectional"))
      (node (ref "OK1") (pin "10") (pinfunction "COL_10") (pintype "passive"))
      (node (ref "R9") (pin "1") (pinfunction "1_1") (pintype "passive"))
    )
    (net (code "35") (name "Net-(IC1-T0CKI{slash}RA4)") (class "Default")
      (node (ref "IC1") (pin "6") (pinfunction "T0CKI/RA4_6") (pintype "bidirectional"))
      (node (ref "OK2") (pin "16") (pinfunction "COL_16") (pintype "passive"))
      (node (ref "R13") (pin "1") (pinfunction "1_1") (pintype "passive"))
    )
    (net (code "36") (name "Net-(IC1-T1CKI{slash}SOSCO{slash}RC0)") (class "Default")
      (node (ref "IC1") (pin "11") (pinfunction "T1CKI/SOSCO/RC0_11") (pintype "bidirectional"))
      (node (ref "OK1") (pin "16") (pinfunction "COL_16") (pintype "passive"))
      (node (ref "R2") (pin "1") (pinfunction "1_1") (pintype "passive"))
    )
    (net (code "37") (name "Net-(IC1-VCAP{slash}~{SS}{slash}AN4{slash}RA5)") (class "Default")
      (node (ref "IC1") (pin "7") (pinfunction "VCAP/~{SS}/AN4/RA5_7") (pintype "bidirectional"))
      (node (ref "OK2") (pin "14") (pinfunction "COL_14") (pintype "passive"))
      (node (ref "R15") (pin "1") (pinfunction "1_1") (pintype "passive"))
    )
    (net (code "38") (name "Net-(IC1-VREF+{slash}AN3{slash}RA3)") (class "Default")
      (node (ref "IC1") (pin "5") (pinfunction "VREF+/AN3/RA3_5") (pintype "bidirectional"))
      (node (ref "OK3") (pin "16") (pinfunction "COL_16") (pintype "passive"))
      (node (ref "R31") (pin "1") (pinfunction "1_1") (pintype "passive"))
    )
    (net (code "39") (name "Net-(IC1-~{SS}{slash}AN0{slash}RA0)") (class "Default")
      (node (ref "IC1") (pin "2") (pinfunction "~{SS}/AN0/RA0_2") (pintype "bidirectional"))
      (node (ref "R28") (pin "1") (pinfunction "1_1") (pintype "passive"))
    )
    (net (code "40") (name "Net-(IC2-DRC)") (class "Default")
      (node (ref "IC2") (pin "1") (pinfunction "SWC_1") (pintype "bidirectional"))
      (node (ref "IC2") (pin "7") (pinfunction "IPK_7") (pintype "bidirectional"))
      (node (ref "IC2") (pin "8") (pinfunction "DRC_8") (pintype "bidirectional"))
      (node (ref "R23") (pin "1") (pinfunction "1_1") (pintype "passive"))
    )
    (net (code "41") (name "Net-(IC2-FB)") (class "Default")
      (node (ref "IC2") (pin "5") (pinfunction "FB_5") (pintype "bidirectional"))
      (node (ref "R21") (pin "2") (pinfunction "2_2") (pintype "passive"))
      (node (ref "R22") (pin "1") (pinfunction "1_1") (pintype "passive"))
    )
    (net (code "42") (name "Net-(IC2-TC)") (class "Default")
      (node (ref "C14") (pin "2") (pinfunction "2_2") (pintype "passive"))
      (node (ref "IC2") (pin "3") (pinfunction "TC_3") (pintype "bidirectional"))
    )
    (net (code "43") (name "Net-(NTRL_IND-P)") (class "Default")
      (node (ref "D12") (pin "A") (pinfunction "A_A") (pintype "passive"))
      (node (ref "NTRL_IND") (pin "1") (pinfunction "P_1") (pintype "passive"))
      (node (ref "R54") (pin "2") (pinfunction "2_2") (pintype "passive"))
    )
    (net (code "44") (name "Net-(OK1A-A)") (class "Default")
      (node (ref "C3") (pin "2") (pinfunction "2_2") (pintype "passive"))
      (node (ref "OK1") (pin "1") (pinfunction "A_1") (pintype "passive"))
      (node (ref "PAD5") (pin "1") (pinfunction "P_1") (pintype "passive"))
      (node (ref "R3") (pin "2") (pinfunction "2_2") (pintype "passive"))
    )
    (net (code "45") (name "Net-(OK1B-A)") (class "Default")
      (node (ref "C5") (pin "2") (pinfunction "2_2") (pintype "passive"))
      (node (ref "OK1") (pin "3") (pinfunction "A_3") (pintype "passive"))
      (node (ref "PAD6") (pin "1") (pinfunction "P_1") (pintype "passive"))
      (node (ref "R6") (pin "2") (pinfunction "2_2") (pintype "passive"))
    )
    (net (code "46") (name "Net-(OK1C-A)") (class "Default")
      (node (ref "C6") (pin "2") (pinfunction "2_2") (pintype "passive"))
      (node (ref "OK1") (pin "5") (pinfunction "A_5") (pintype "passive"))
      (node (ref "PAD7") (pin "1") (pinfunction "P_1") (pintype "passive"))
      (node (ref "R8") (pin "2") (pinfunction "2_2") (pintype "passive"))
    )
    (net (code "47") (name "Net-(OK1D-A)") (class "Default")
      (node (ref "C7") (pin "2") (pinfunction "2_2") (pintype "passive"))
      (node (ref "OK1") (pin "7") (pinfunction "A_7") (pintype "passive"))
      (node (ref "PAD8") (pin "1") (pinfunction "P_1") (pintype "passive"))
      (node (ref "R10") (pin "2") (pinfunction "2_2") (pintype "passive"))
    )
    (net (code "48") (name "Net-(OK3B-A)") (class "Default")
      (node (ref "OK3") (pin "3") (pinfunction "A_3") (pintype "passive"))
      (node (ref "R30") (pin "2") (pinfunction "2_2") (pintype "passive"))
    )
    (net (code "49") (name "Net-(OK3B-EMIT)") (class "Default")
      (node (ref "OK3") (pin "13") (pinfunction "EMIT_13") (pintype "passive"))
      (node (ref "R46") (pin "1") (pinfunction "1_1") (pintype "passive"))
      (node (ref "R47") (pin "1") (pinfunction "1_1") (pintype "passive"))
    )
    (net (code "50") (name "Net-(OK3C-A)") (class "Default")
      (node (ref "OK3") (pin "5") (pinfunction "A_5") (pintype "passive"))
      (node (ref "R29") (pin "2") (pinfunction "2_2") (pintype "passive"))
    )
    (net (code "51") (name "Net-(OK3C-EMIT)") (class "Default")
      (node (ref "OK3") (pin "11") (pinfunction "EMIT_11") (pintype "passive"))
      (node (ref "R44") (pin "1") (pinfunction "1_1") (pintype "passive"))
      (node (ref "R45") (pin "1") (pinfunction "1_1") (pintype "passive"))
    )
    (net (code "52") (name "Net-(OK3D-A)") (class "Default")
      (node (ref "OK3") (pin "7") (pinfunction "A_7") (pintype "passive"))
      (node (ref "R28") (pin "2") (pinfunction "2_2") (pintype "passive"))
    )
    (net (code "53") (name "Net-(OK3D-EMIT)") (class "Default")
      (node (ref "OK3") (pin "9") (pinfunction "EMIT_9") (pintype "passive"))
      (node (ref "R48") (pin "1") (pinfunction "1_1") (pintype "passive"))
      (node (ref "R49") (pin "1") (pinfunction "1_1") (pintype "passive"))
    )
    (net (code "54") (name "Net-(OK4A-A)") (class "Default")
      (node (ref "OK4") (pin "1") (pinfunction "A_1") (pintype "passive"))
      (node (ref "R27") (pin "2") (pinfunction "2_2") (pintype "passive"))
    )
    (net (code "55") (name "Net-(OK4A-EMIT)") (class "Default")
      (node (ref "OK4") (pin "15") (pinfunction "EMIT_15") (pintype "passive"))
      (node (ref "R52") (pin "1") (pinfunction "1_1") (pintype "passive"))
      (node (ref "R53") (pin "1") (pinfunction "1_1") (pintype "passive"))
    )
    (net (code "56") (name "Net-(OK4B-A)") (class "Default")
      (node (ref "OK4") (pin "3") (pinfunction "A_3") (pintype "passive"))
      (node (ref "R26") (pin "2") (pinfunction "2_2") (pintype "passive"))
    )
    (net (code "57") (name "Net-(OK4B-EMIT)") (class "Default")
      (node (ref "OK4") (pin "13") (pinfunction "EMIT_13") (pintype "passive"))
      (node (ref "R50") (pin "1") (pinfunction "1_1") (pintype "passive"))
      (node (ref "R51") (pin "1") (pinfunction "1_1") (pintype "passive"))
    )
    (net (code "58") (name "Net-(OK4C-A)") (class "Default")
      (node (ref "OK4") (pin "5") (pinfunction "A_5") (pintype "passive"))
      (node (ref "R25") (pin "2") (pinfunction "2_2") (pintype "passive"))
    )
    (net (code "59") (name "Net-(OK4C-EMIT)") (class "Default")
      (node (ref "OK4") (pin "11") (pinfunction "EMIT_11") (pintype "passive"))
      (node (ref "R40") (pin "1") (pinfunction "1_1") (pintype "passive"))
      (node (ref "R41") (pin "1") (pinfunction "1_1") (pintype "passive"))
    )
    (net (code "60") (name "Net-(OK4D-A)") (class "Default")
      (node (ref "OK4") (pin "7") (pinfunction "A_7") (pintype "passive"))
      (node (ref "R24") (pin "2") (pinfunction "2_2") (pintype "passive"))
    )
    (net (code "61") (name "Net-(OK4D-EMIT)") (class "Default")
      (node (ref "OK4") (pin "9") (pinfunction "EMIT_9") (pintype "passive"))
      (node (ref "R42") (pin "1") (pinfunction "1_1") (pintype "passive"))
      (node (ref "R43") (pin "1") (pinfunction "1_1") (pintype "passive"))
    )
    (net (code "62") (name "Net-(PAD2-P)") (class "Default")
      (node (ref "B1") (pin "AC2") (pinfunction "AC2_AC2") (pintype "passive"))
      (node (ref "PAD2") (pin "1") (pinfunction "P_1") (pintype "passive"))
    )
    (net (code "63") (name "Net-(PAD9-P)") (class "Default")
      (node (ref "D2") (pin "A") (pinfunction "A_A") (pintype "passive"))
      (node (ref "PAD9") (pin "1") (pinfunction "P_1") (pintype "passive"))
    )
    (net (code "64") (name "Net-(PAD12-P)") (class "Default")
      (node (ref "D4") (pin "A") (pinfunction "A_A") (pintype "passive"))
      (node (ref "PAD12") (pin "1") (pinfunction "P_1") (pintype "passive"))
    )
    (net (code "65") (name "Net-(PAD13-P)") (class "Default")
      (node (ref "D6") (pin "A") (pinfunction "A_A") (pintype "passive"))
      (node (ref "PAD13") (pin "1") (pinfunction "P_1") (pintype "passive"))
    )
    (net (code "66") (name "Net-(PAD14-P)") (class "Default")
      (node (ref "D9") (pin "A") (pinfunction "A_A") (pintype "passive"))
      (node (ref "PAD14") (pin "1") (pinfunction "P_1") (pintype "passive"))
    )
    (net (code "67") (name "Net-(PAD15-P)") (class "Default")
      (node (ref "D11") (pin "A") (pinfunction "A_A") (pintype "passive"))
      (node (ref "PAD15") (pin "1") (pinfunction "P_1") (pintype "passive"))
    )
    (net (code "68") (name "Net-(PARK_BRK_IND-P)") (class "Default")
      (node (ref "PARK_BRK_IND") (pin "1") (pinfunction "P_1") (pintype "passive"))
      (node (ref "Q2") (pin "2") (pinfunction "S_2") (pintype "passive"))
    )
    (net (code "69") (name "Net-(PTO_SOL-P)") (class "Default")
      (node (ref "PTO_SOL") (pin "1") (pinfunction "P_1") (pintype "passive"))
      (node (ref "Q6") (pin "3") (pinfunction "S_3") (pintype "passive"))
    )
    (net (code "70") (name "Net-(Q1-D)") (class "Default")
      (node (ref "Q1") (pin "3") (pinfunction "D_3") (pintype "passive"))
      (node (ref "R54") (pin "1") (pinfunction "1_1") (pintype "passive"))
    )
    (net (code "71") (name "Net-(Q1-G)") (class "Default")
      (node (ref "C19") (pin "2") (pinfunction "2_2") (pintype "passive"))
      (node (ref "Q1") (pin "1") (pinfunction "G_1") (pintype "passive"))
      (node (ref "R40") (pin "2") (pinfunction "2_2") (pintype "passive"))
    )
    (net (code "72") (name "Net-(Q2-D)") (class "Default")
      (node (ref "Q2") (pin "3") (pinfunction "D_3") (pintype "passive"))
      (node (ref "R55") (pin "1") (pinfunction "1_1") (pintype "passive"))
    )
    (net (code "73") (name "Net-(Q2-G)") (class "Default")
      (node (ref "C20") (pin "2") (pinfunction "2_2") (pintype "passive"))
      (node (ref "Q2") (pin "1") (pinfunction "G_1") (pintype "passive"))
      (node (ref "R42") (pin "2") (pinfunction "2_2") (pintype "passive"))
    )
    (net (code "74") (name "Net-(Q3-D)") (class "Default")
      (node (ref "Q3") (pin "3") (pinfunction "D_3") (pintype "passive"))
      (node (ref "R56") (pin "1") (pinfunction "1_1") (pintype "passive"))
    )
    (net (code "75") (name "Net-(Q3-G)") (class "Default")
      (node (ref "C21") (pin "2") (pinfunction "2_2") (pintype "passive"))
      (node (ref "Q3") (pin "1") (pinfunction "G_1") (pintype "passive"))
      (node (ref "R44") (pin "2") (pinfunction "2_2") (pintype "passive"))
    )
    (net (code "76") (name "Net-(Q4-D)") (class "Default")
      (node (ref "Q4") (pin "3") (pinfunction "D_3") (pintype "passive"))
      (node (ref "R57") (pin "1") (pinfunction "1_1") (pintype "passive"))
    )
    (net (code "77") (name "Net-(Q4-G)") (class "Default")
      (node (ref "C22") (pin "2") (pinfunction "2_2") (pintype "passive"))
      (node (ref "Q4") (pin "1") (pinfunction "G_1") (pintype "passive"))
      (node (ref "R46") (pin "2") (pinfunction "2_2") (pintype "passive"))
    )
    (net (code "78") (name "Net-(Q4-S)") (class "Default")
      (node (ref "Q4") (pin "2") (pinfunction "S_2") (pintype "passive"))
      (node (ref "STRT_MOT") (pin "1") (pinfunction "P_1") (pintype "passive"))
    )
    (net (code "79") (name "Net-(Q5-D)") (class "Default")
      (node (ref "Q5") (pin "3") (pinfunction "D_3") (pintype "passive"))
      (node (ref "R58") (pin "1") (pinfunction "1_1") (pintype "passive"))
    )
    (net (code "80") (name "Net-(Q5-G)") (class "Default")
      (node (ref "C23") (pin "2") (pinfunction "2_2") (pintype "passive"))
      (node (ref "Q5") (pin "1") (pinfunction "G_1") (pintype "passive"))
      (node (ref "R48") (pin "2") (pinfunction "2_2") (pintype "passive"))
    )
    (net (code "81") (name "Net-(Q5-S)") (class "Default")
      (node (ref "Q5") (pin "2") (pinfunction "S_2") (pintype "passive"))
      (node (ref "STRT_REL_COIL") (pin "1") (pinfunction "P_1") (pintype "passive"))
    )
    (net (code "82") (name "Net-(Q6-G)") (class "Default")
      (node (ref "C24") (pin "2") (pinfunction "2_2") (pintype "passive"))
      (node (ref "Q6") (pin "1") (pinfunction "G_1") (pintype "passive"))
      (node (ref "R50") (pin "2") (pinfunction "2_2") (pintype "passive"))
    )
    (net (code "83") (name "Net-(Q7-G)") (class "Default")
      (node (ref "C25") (pin "2") (pinfunction "2_2") (pintype "passive"))
      (node (ref "Q7") (pin "1") (pinfunction "G_1") (pintype "passive"))
      (node (ref "R52") (pin "2") (pinfunction "2_2") (pintype "passive"))
    )
    (net (code "84") (name "Net-(R11-Pad2)") (class "Default")
      (node (ref "R11") (pin "2") (pinfunction "2_2") (pintype "passive"))
      (node (ref "R12") (pin "1") (pinfunction "1_1") (pintype "passive"))
    )
    (net (code "85") (name "VCC") (class "Default")
      (node (ref "C12") (pin "2") (pinfunction "2_2") (pintype "passive"))
      (node (ref "C15") (pin "1") (pinfunction "1_1") (pintype "passive"))
      (node (ref "C17") (pin "2") (pinfunction "2_2") (pintype "passive"))
      (node (ref "IC1") (pin "20") (pinfunction "VDD_20") (pintype "power_in"))
      (node (ref "L2") (pin "1") (pinfunction "1_1") (pintype "passive"))
      (node (ref "OK3") (pin "10") (pinfunction "COL_10") (pintype "passive"))
      (node (ref "OK3") (pin "12") (pinfunction "COL_12") (pintype "passive"))
      (node (ref "OK3") (pin "14") (pinfunction "COL_14") (pintype "passive"))
      (node (ref "OK4") (pin "10") (pinfunction "COL_10") (pintype "passive"))
      (node (ref "OK4") (pin "12") (pinfunction "COL_12") (pintype "passive"))
      (node (ref "OK4") (pin "14") (pinfunction "COL_14") (pintype "passive"))
      (node (ref "OK4") (pin "16") (pinfunction "COL_16") (pintype "passive"))
      (node (ref "R1") (pin "1") (pinfunction "1_1") (pintype "passive"))
      (node (ref "R13") (pin "2") (pinfunction "2_2") (pintype "passive"))
      (node (ref "R15") (pin "2") (pinfunction "2_2") (pintype "passive"))
      (node (ref "R17") (pin "2") (pinfunction "2_2") (pintype "passive"))
      (node (ref "R19") (pin "2") (pinfunction "2_2") (pintype "passive"))
      (node (ref "R2") (pin "2") (pinfunction "2_2") (pintype "passive"))
      (node (ref "R21") (pin "1") (pinfunction "1_1") (pintype "passive"))
      (node (ref "R31") (pin "2") (pinfunction "2_2") (pintype "passive"))
      (node (ref "R5") (pin "2") (pinfunction "2_2") (pintype "passive"))
      (node (ref "R7") (pin "2") (pinfunction "2_2") (pintype "passive"))
      (node (ref "R9") (pin "2") (pinfunction "2_2") (pintype "passive"))
      (node (ref "VCC") (pin "1") (pinfunction "P_1") (pintype "passive"))
    )
    (net (code "86") (name "VDD") (class "Default")
      (node (ref "C10") (pin "2") (pinfunction "2_2") (pintype "passive"))
      (node (ref "C9") (pin "1") (pinfunction "1_1") (pintype "passive"))
      (node (ref "IC2") (pin "6") (pinfunction "VCC_6") (pintype "bidirectional"))
      (node (ref "R10") (pin "1") (pinfunction "1_1") (pintype "passive"))
      (node (ref "R12") (pin "2") (pinfunction "2_2") (pintype "passive"))
      (node (ref "R23") (pin "2") (pinfunction "2_2") (pintype "passive"))
      (node (ref "R3") (pin "1") (pinfunction "1_1") (pintype "passive"))
      (node (ref "R6") (pin "1") (pinfunction "1_1") (pintype "passive"))
      (node (ref "R8") (pin "1") (pinfunction "1_1") (pintype "passive"))
    )
    (net (code "87") (name "unconnected-(IC1-RB4{slash}AN11-Pad25)") (class "Default")
      (node (ref "IC1") (pin "25") (pinfunction "RB4/AN11_25") (pintype "bidirectional"))
    )
    (net (code "88") (name "unconnected-(IC1-RB5{slash}AN13{slash}T1G-Pad26)") (class "Default")
      (node (ref "IC1") (pin "26") (pinfunction "RB5/AN13/T1G_26") (pintype "bidirectional"))
    )
    (net (code "89") (name "unconnected-(IC1-RC4{slash}AN16{slash}SDI{slash}SDA-Pad15)") (class "Default")
      (node (ref "IC1") (pin "15") (pinfunction "RC4/AN16/SDI/SDA_15") (pintype "bidirectional"))
    )
    (net (code "90") (name "unconnected-(IC1-RC5{slash}AN17{slash}SDO-Pad16)") (class "Default")
      (node (ref "IC1") (pin "16") (pinfunction "RC5/AN17/SDO_16") (pintype "bidirectional"))
    )
  )
)
